# M402X.net
KiCad netlist of a schematic drawn in EAGLE
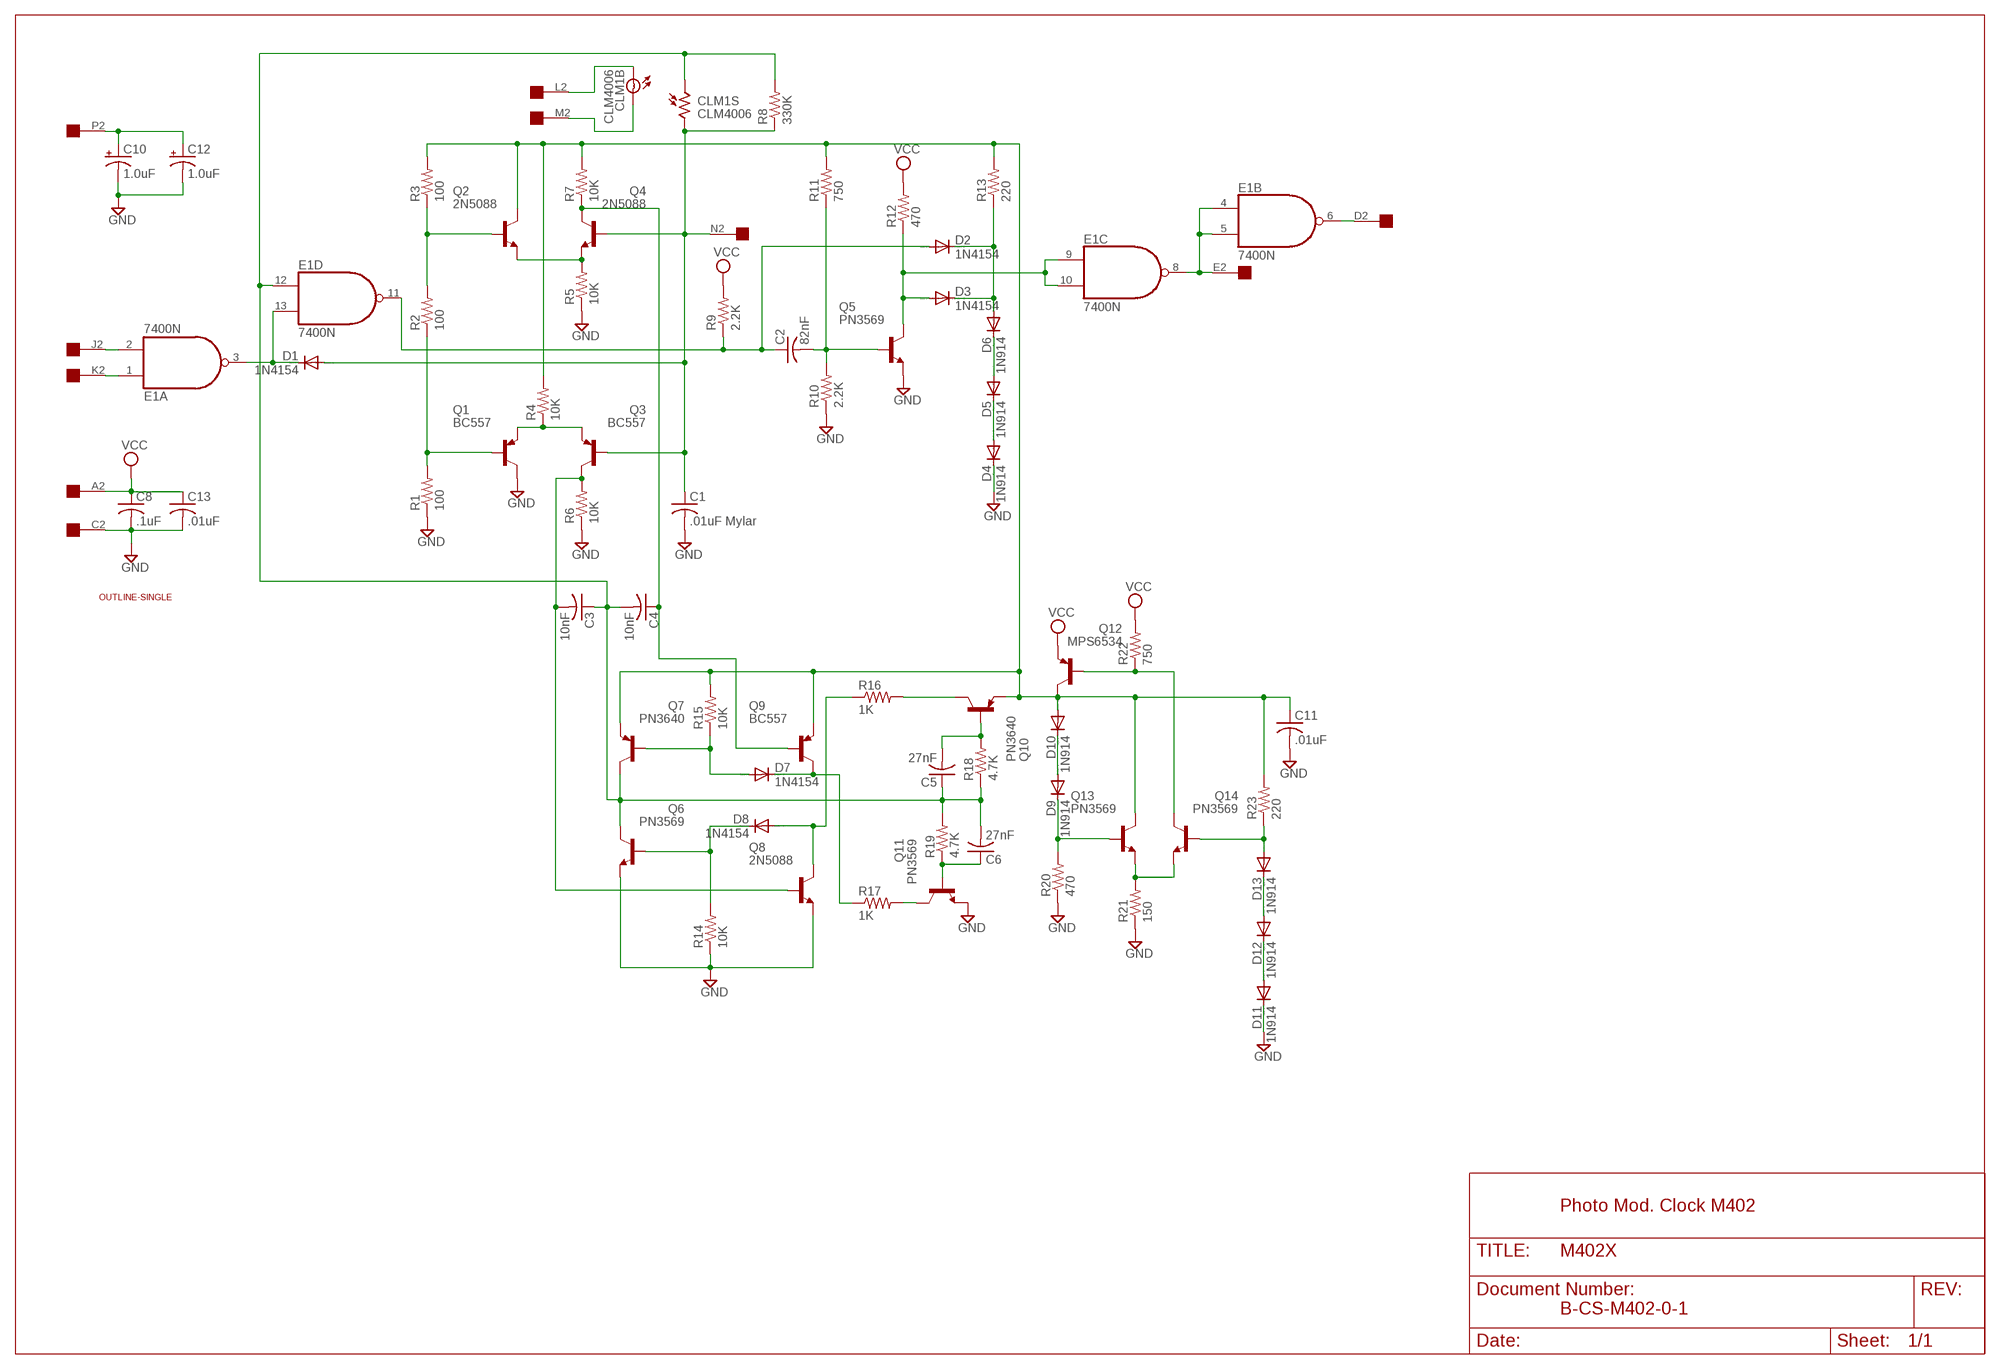
[diagram p0: schematic, sheet 1]

(export (version "E")
  (design (tool "Eeschema 10.0.6"))
  (components
    (comp (ref "C1")
      (value ".01uF Mylar")
      (footprint "eagle-import:C225-062X268")
      (libsource (lib "eagle-import") (part "C-US225-062X268"))
    )
    (comp (ref "C2")
      (value "82nF")
      (footprint "eagle-import:C050-025X075")
      (libsource (lib "eagle-import") (part "C-US050-025X075"))
    )
    (comp (ref "C3")
      (value "10nF")
      (footprint "eagle-import:C075-032X103")
      (libsource (lib "eagle-import") (part "C-US075-032X103"))
    )
    (comp (ref "C4")
      (value "10nF")
      (footprint "eagle-import:C075-032X103")
      (libsource (lib "eagle-import") (part "C-US075-032X103"))
    )
    (comp (ref "C5")
      (value "27nF")
      (footprint "eagle-import:C075-032X103")
      (libsource (lib "eagle-import") (part "C-US075-032X103"))
    )
    (comp (ref "C6")
      (value "27nF")
      (footprint "eagle-import:C075-032X103")
      (libsource (lib "eagle-import") (part "C-US075-032X103"))
    )
    (comp (ref "C8")
      (value ".1uF")
      (footprint "eagle-import:C075-032X103")
      (libsource (lib "eagle-import") (part "C-US075-032X103"))
    )
    (comp (ref "C10")
      (value "1.0uF")
      (footprint "eagle-import:E15-5")
      (libsource (lib "eagle-import") (part "CPOL-USE15-5AXIAL"))
    )
    (comp (ref "C11")
      (value ".01uF")
      (footprint "eagle-import:C050-025X075")
      (libsource (lib "eagle-import") (part "C-US050-025X075"))
    )
    (comp (ref "C12")
      (value "1.0uF")
      (footprint "eagle-import:E15-5")
      (libsource (lib "eagle-import") (part "CPOL-USE15-5AXIAL"))
    )
    (comp (ref "C13")
      (value ".01uF")
      (footprint "eagle-import:C102-043X133")
      (libsource (lib "eagle-import") (part "C-US102-043X133"))
    )
    (comp (ref "CLM1")
      (value "CLM4006")
      (footprint "eagle-import:CLM4006")
      (libsource (lib "eagle-import") (part "CLM4006"))
    )
    (comp (ref "D1")
      (value "1N4154")
      (footprint "eagle-import:DO35-10")
      (libsource (lib "eagle-import") (part "DIODE-DO35-10"))
    )
    (comp (ref "D2")
      (value "1N4154")
      (footprint "eagle-import:DO35-10")
      (libsource (lib "eagle-import") (part "DIODE-DO35-10"))
    )
    (comp (ref "D3")
      (value "1N4154")
      (footprint "eagle-import:DO35-10")
      (libsource (lib "eagle-import") (part "DIODE-DO35-10"))
    )
    (comp (ref "D4")
      (value "1N914")
      (footprint "eagle-import:DO35-10")
      (libsource (lib "eagle-import") (part "DIODE-DO35-10"))
    )
    (comp (ref "D5")
      (value "1N914")
      (footprint "eagle-import:DO35-10")
      (libsource (lib "eagle-import") (part "DIODE-DO35-10"))
    )
    (comp (ref "D6")
      (value "1N914")
      (footprint "eagle-import:DO35-10")
      (libsource (lib "eagle-import") (part "DIODE-DO35-10"))
    )
    (comp (ref "D7")
      (value "1N4154")
      (footprint "eagle-import:DO35-10")
      (libsource (lib "eagle-import") (part "DIODE-DO35-10"))
    )
    (comp (ref "D8")
      (value "1N4154")
      (footprint "eagle-import:DO35-10")
      (libsource (lib "eagle-import") (part "DIODE-DO35-10"))
    )
    (comp (ref "D9")
      (value "1N914")
      (footprint "eagle-import:DO35-10")
      (libsource (lib "eagle-import") (part "DIODE-DO35-10"))
    )
    (comp (ref "D10")
      (value "1N914")
      (footprint "eagle-import:DO35-10")
      (libsource (lib "eagle-import") (part "DIODE-DO35-10"))
    )
    (comp (ref "D11")
      (value "1N914")
      (footprint "eagle-import:DO35-10")
      (libsource (lib "eagle-import") (part "DIODE-DO35-10"))
    )
    (comp (ref "D12")
      (value "1N914")
      (footprint "eagle-import:DO35-10")
      (libsource (lib "eagle-import") (part "DIODE-DO35-10"))
    )
    (comp (ref "D13")
      (value "1N914")
      (footprint "eagle-import:DO35-10")
      (libsource (lib "eagle-import") (part "DIODE-DO35-10"))
    )
    (comp (ref "E1")
      (value "7400N")
      (footprint "eagle-import:DIL14")
      (libsource (lib "eagle-import") (part "7400N"))
    )
    (comp (ref "Q1")
      (value "BC557")
      (footprint "eagle-import:TO5")
      (libsource (lib "eagle-import") (part "-PNP-TO5"))
    )
    (comp (ref "Q2")
      (value "2N5088")
      (footprint "eagle-import:TO5")
      (libsource (lib "eagle-import") (part "-NPN-TO5"))
    )
    (comp (ref "Q3")
      (value "BC557")
      (footprint "eagle-import:TO5")
      (libsource (lib "eagle-import") (part "-PNP-TO5"))
    )
    (comp (ref "Q4")
      (value "2N5088")
      (footprint "eagle-import:TO5")
      (libsource (lib "eagle-import") (part "-NPN-TO5"))
    )
    (comp (ref "Q5")
      (value "PN3569")
      (footprint "eagle-import:TO5")
      (libsource (lib "eagle-import") (part "-NPN-TO5"))
    )
    (comp (ref "Q6")
      (value "PN3569")
      (footprint "eagle-import:TO5")
      (libsource (lib "eagle-import") (part "-NPN-TO5"))
    )
    (comp (ref "Q7")
      (value "PN3640")
      (footprint "eagle-import:TO5")
      (libsource (lib "eagle-import") (part "-PNP-TO5"))
    )
    (comp (ref "Q8")
      (value "2N5088")
      (footprint "eagle-import:TO5")
      (libsource (lib "eagle-import") (part "-NPN-TO5"))
    )
    (comp (ref "Q9")
      (value "BC557")
      (footprint "eagle-import:TO5")
      (libsource (lib "eagle-import") (part "-PNP-TO5"))
    )
    (comp (ref "Q10")
      (value "PN3640")
      (footprint "eagle-import:TO5")
      (libsource (lib "eagle-import") (part "-PNP-TO5"))
    )
    (comp (ref "Q11")
      (value "PN3569")
      (footprint "eagle-import:TO5")
      (libsource (lib "eagle-import") (part "-NPN-TO5"))
    )
    (comp (ref "Q12")
      (value "MPS6534")
      (footprint "eagle-import:TO5")
      (libsource (lib "eagle-import") (part "-PNP-TO5"))
    )
    (comp (ref "Q13")
      (value "PN3569")
      (footprint "eagle-import:TO5")
      (libsource (lib "eagle-import") (part "-NPN-TO5"))
    )
    (comp (ref "Q14")
      (value "PN3569")
      (footprint "eagle-import:TO5")
      (libsource (lib "eagle-import") (part "-NPN-TO5"))
    )
    (comp (ref "R1")
      (value "100")
      (footprint "eagle-import:0207_10")
      (libsource (lib "eagle-import") (part "R-US_0207/10"))
    )
    (comp (ref "R2")
      (value "100")
      (footprint "eagle-import:0207_10")
      (libsource (lib "eagle-import") (part "R-US_0207/10"))
    )
    (comp (ref "R3")
      (value "100")
      (footprint "eagle-import:0207_10")
      (libsource (lib "eagle-import") (part "R-US_0207/10"))
    )
    (comp (ref "R4")
      (value "10K")
      (footprint "eagle-import:0207_10")
      (libsource (lib "eagle-import") (part "R-US_0207/10"))
    )
    (comp (ref "R5")
      (value "10K")
      (footprint "eagle-import:0207_10")
      (libsource (lib "eagle-import") (part "R-US_0207/10"))
    )
    (comp (ref "R6")
      (value "10K")
      (footprint "eagle-import:0207_10")
      (libsource (lib "eagle-import") (part "R-US_0207/10"))
    )
    (comp (ref "R7")
      (value "10K")
      (footprint "eagle-import:0207_10")
      (libsource (lib "eagle-import") (part "R-US_0207/10"))
    )
    (comp (ref "R8")
      (value "330K")
      (footprint "eagle-import:0207_10")
      (libsource (lib "eagle-import") (part "R-US_0207/10"))
    )
    (comp (ref "R9")
      (value "2.2K")
      (footprint "eagle-import:0207_10")
      (libsource (lib "eagle-import") (part "R-US_0207/10"))
    )
    (comp (ref "R10")
      (value "2.2K")
      (footprint "eagle-import:0207_10")
      (libsource (lib "eagle-import") (part "R-US_0207/10"))
    )
    (comp (ref "R11")
      (value "750")
      (footprint "eagle-import:0207_10")
      (libsource (lib "eagle-import") (part "R-US_0207/10"))
    )
    (comp (ref "R12")
      (value "470")
      (footprint "eagle-import:0207_10")
      (libsource (lib "eagle-import") (part "R-US_0207/10"))
    )
    (comp (ref "R13")
      (value "220")
      (footprint "eagle-import:0207_10")
      (libsource (lib "eagle-import") (part "R-US_0207/10"))
    )
    (comp (ref "R14")
      (value "10K")
      (footprint "eagle-import:0207_10")
      (libsource (lib "eagle-import") (part "R-US_0207/10"))
    )
    (comp (ref "R15")
      (value "10K")
      (footprint "eagle-import:0207_10")
      (libsource (lib "eagle-import") (part "R-US_0207/10"))
    )
    (comp (ref "R16")
      (value "1K")
      (footprint "eagle-import:0207_10")
      (libsource (lib "eagle-import") (part "R-US_0207/10"))
    )
    (comp (ref "R17")
      (value "1K")
      (footprint "eagle-import:0207_10")
      (libsource (lib "eagle-import") (part "R-US_0207/10"))
    )
    (comp (ref "R18")
      (value "4.7K")
      (footprint "eagle-import:0207_10")
      (libsource (lib "eagle-import") (part "R-US_0207/10"))
    )
    (comp (ref "R19")
      (value "4.7K")
      (footprint "eagle-import:0207_10")
      (libsource (lib "eagle-import") (part "R-US_0207/10"))
    )
    (comp (ref "R20")
      (value "470")
      (footprint "eagle-import:0207_10")
      (libsource (lib "eagle-import") (part "R-US_0207/10"))
    )
    (comp (ref "R21")
      (value "150")
      (footprint "eagle-import:0207_10")
      (libsource (lib "eagle-import") (part "R-US_0207/10"))
    )
    (comp (ref "R22")
      (value "750")
      (footprint "eagle-import:0207_10")
      (libsource (lib "eagle-import") (part "R-US_0207/10"))
    )
    (comp (ref "R23")
      (value "220")
      (footprint "eagle-import:0207_10")
      (libsource (lib "eagle-import") (part "R-US_0207/10"))
    )
    (comp (ref "U$1")
      (value "OUTLINE-SINGLE")
      (footprint "eagle-import:SINGLE")
      (libsource (lib "eagle-import") (part "OUTLINE-SINGLE"))
    )
    (comp (ref "U$3")
      (value "EDGE-1")
      (footprint "eagle-import:EDGE-CON1")
      (libsource (lib "eagle-import") (part "EDGE-1"))
    )
  )
  (nets
    (net (code "1") (name "GND") (class "Default")
      (node (ref "C1") (pin "2") (pinfunction "2_2") (pintype "passive"))
      (node (ref "C10") (pin "-") (pinfunction "-_-") (pintype "passive"))
      (node (ref "C11") (pin "2") (pinfunction "2_2") (pintype "passive"))
      (node (ref "C12") (pin "-") (pinfunction "-_-") (pintype "passive"))
      (node (ref "C13") (pin "2") (pinfunction "2_2") (pintype "passive"))
      (node (ref "C8") (pin "2") (pinfunction "2_2") (pintype "passive"))
      (node (ref "D11") (pin "C") (pinfunction "C_C") (pintype "passive"))
      (node (ref "D4") (pin "C") (pinfunction "C_C") (pintype "passive"))
      (node (ref "Q1") (pin "3") (pinfunction "C_3") (pintype "passive"))
      (node (ref "Q11") (pin "1") (pinfunction "E_1") (pintype "passive"))
      (node (ref "Q5") (pin "1") (pinfunction "E_1") (pintype "passive"))
      (node (ref "Q6") (pin "1") (pinfunction "E_1") (pintype "passive"))
      (node (ref "Q8") (pin "1") (pinfunction "E_1") (pintype "passive"))
      (node (ref "R1") (pin "1") (pinfunction "1_1") (pintype "passive"))
      (node (ref "R10") (pin "1") (pinfunction "1_1") (pintype "passive"))
      (node (ref "R14") (pin "1") (pinfunction "1_1") (pintype "passive"))
      (node (ref "R20") (pin "1") (pinfunction "1_1") (pintype "passive"))
      (node (ref "R21") (pin "1") (pinfunction "1_1") (pintype "passive"))
      (node (ref "R5") (pin "1") (pinfunction "1_1") (pintype "passive"))
      (node (ref "R6") (pin "1") (pinfunction "1_1") (pintype "passive"))
      (node (ref "U$3") (pin "C2") (pinfunction "1_C2") (pintype "bidirectional"))
    )
    (net (code "2") (name "Net-(CLM1A-A)") (class "Default")
      (node (ref "CLM1") (pin "B1") (pinfunction "A_B1") (pintype "passive"))
      (node (ref "U$3") (pin "M2") (pinfunction "1_M2") (pintype "bidirectional"))
    )
    (net (code "3") (name "Net-(CLM1A-B)") (class "Default")
      (node (ref "CLM1") (pin "B2") (pinfunction "B_B2") (pintype "passive"))
      (node (ref "U$3") (pin "L2") (pinfunction "1_L2") (pintype "bidirectional"))
    )
    (net (code "4") (name "Net-(CLM1B-1)") (class "Default")
      (node (ref "C3") (pin "1") (pinfunction "1_1") (pintype "passive"))
      (node (ref "C4") (pin "2") (pinfunction "2_2") (pintype "passive"))
      (node (ref "C5") (pin "1") (pinfunction "1_1") (pintype "passive"))
      (node (ref "C6") (pin "2") (pinfunction "2_2") (pintype "passive"))
      (node (ref "CLM1") (pin "S1") (pinfunction "1_S1") (pintype "passive"))
      (node (ref "E1") (pin "12") (pinfunction "I0_12") (pintype "input"))
      (node (ref "Q6") (pin "3") (pinfunction "C_3") (pintype "passive"))
      (node (ref "Q7") (pin "3") (pinfunction "C_3") (pintype "passive"))
      (node (ref "R18") (pin "1") (pinfunction "1_1") (pintype "passive"))
      (node (ref "R19") (pin "2") (pinfunction "2_2") (pintype "passive"))
      (node (ref "R8") (pin "2") (pinfunction "2_2") (pintype "passive"))
    )
    (net (code "5") (name "Net-(CLM1B-2)") (class "Default")
      (node (ref "C1") (pin "1") (pinfunction "1_1") (pintype "passive"))
      (node (ref "CLM1") (pin "S2") (pinfunction "2_S2") (pintype "passive"))
      (node (ref "D1") (pin "A") (pinfunction "A_A") (pintype "passive"))
      (node (ref "Q3") (pin "2") (pinfunction "B_2") (pintype "passive"))
      (node (ref "Q4") (pin "2") (pinfunction "B_2") (pintype "passive"))
      (node (ref "R8") (pin "1") (pinfunction "1_1") (pintype "passive"))
      (node (ref "U$3") (pin "N2") (pinfunction "1_N2") (pintype "bidirectional"))
    )
    (net (code "6") (name "Net-(D2-PadC)") (class "Default")
      (node (ref "D2") (pin "C") (pinfunction "C_C") (pintype "passive"))
      (node (ref "D3") (pin "C") (pinfunction "C_C") (pintype "passive"))
      (node (ref "D6") (pin "A") (pinfunction "A_A") (pintype "passive"))
      (node (ref "R13") (pin "1") (pinfunction "1_1") (pintype "passive"))
    )
    (net (code "7") (name "Net-(D4-PadA)") (class "Default")
      (node (ref "D4") (pin "A") (pinfunction "A_A") (pintype "passive"))
      (node (ref "D5") (pin "C") (pinfunction "C_C") (pintype "passive"))
    )
    (net (code "8") (name "Net-(D5-PadA)") (class "Default")
      (node (ref "D5") (pin "A") (pinfunction "A_A") (pintype "passive"))
      (node (ref "D6") (pin "C") (pinfunction "C_C") (pintype "passive"))
    )
    (net (code "9") (name "Net-(D10-PadC)") (class "Default")
      (node (ref "D10") (pin "C") (pinfunction "C_C") (pintype "passive"))
      (node (ref "D9") (pin "A") (pinfunction "A_A") (pintype "passive"))
    )
    (net (code "10") (name "Net-(D11-PadA)") (class "Default")
      (node (ref "D11") (pin "A") (pinfunction "A_A") (pintype "passive"))
      (node (ref "D12") (pin "C") (pinfunction "C_C") (pintype "passive"))
    )
    (net (code "11") (name "Net-(D12-PadA)") (class "Default")
      (node (ref "D12") (pin "A") (pinfunction "A_A") (pintype "passive"))
      (node (ref "D13") (pin "C") (pinfunction "C_C") (pintype "passive"))
    )
    (net (code "12") (name "Net-(E1A-I0)") (class "Default")
      (node (ref "E1") (pin "1") (pinfunction "I0_1") (pintype "input"))
      (node (ref "U$3") (pin "K2") (pinfunction "1_K2") (pintype "bidirectional"))
    )
    (net (code "13") (name "Net-(E1A-I1)") (class "Default")
      (node (ref "E1") (pin "2") (pinfunction "I1_2") (pintype "input"))
      (node (ref "U$3") (pin "J2") (pinfunction "1_J2") (pintype "bidirectional"))
    )
    (net (code "14") (name "Net-(E1A-O)") (class "Default")
      (node (ref "D1") (pin "C") (pinfunction "C_C") (pintype "passive"))
      (node (ref "E1") (pin "13") (pinfunction "I1_13") (pintype "input"))
      (node (ref "E1") (pin "3") (pinfunction "O_3") (pintype "output"))
    )
    (net (code "15") (name "Net-(E1B-I0)") (class "Default")
      (node (ref "E1") (pin "4") (pinfunction "I0_4") (pintype "input"))
      (node (ref "E1") (pin "5") (pinfunction "I1_5") (pintype "input"))
      (node (ref "E1") (pin "8") (pinfunction "O_8") (pintype "output"))
      (node (ref "U$3") (pin "E2") (pinfunction "1_E2") (pintype "bidirectional"))
    )
    (net (code "16") (name "Net-(E1B-O)") (class "Default")
      (node (ref "E1") (pin "6") (pinfunction "O_6") (pintype "output"))
      (node (ref "U$3") (pin "D2") (pinfunction "1_D2") (pintype "bidirectional"))
    )
    (net (code "17") (name "Net-(E1C-I0)") (class "Default")
      (node (ref "D3") (pin "A") (pinfunction "A_A") (pintype "passive"))
      (node (ref "E1") (pin "10") (pinfunction "I1_10") (pintype "input"))
      (node (ref "E1") (pin "9") (pinfunction "I0_9") (pintype "input"))
      (node (ref "Q5") (pin "3") (pinfunction "C_3") (pintype "passive"))
      (node (ref "R12") (pin "1") (pinfunction "1_1") (pintype "passive"))
    )
    (net (code "18") (name "Net-(E1D-O)") (class "Default")
      (node (ref "C2") (pin "1") (pinfunction "1_1") (pintype "passive"))
      (node (ref "D2") (pin "A") (pinfunction "A_A") (pintype "passive"))
      (node (ref "E1") (pin "11") (pinfunction "O_11") (pintype "output"))
      (node (ref "R9") (pin "1") (pinfunction "1_1") (pintype "passive"))
    )
    (net (code "19") (name "Net-(Q1-B)") (class "Default")
      (node (ref "Q1") (pin "2") (pinfunction "B_2") (pintype "passive"))
      (node (ref "R1") (pin "2") (pinfunction "2_2") (pintype "passive"))
      (node (ref "R2") (pin "1") (pinfunction "1_1") (pintype "passive"))
    )
    (net (code "20") (name "Net-(Q1-E)") (class "Default")
      (node (ref "Q1") (pin "1") (pinfunction "E_1") (pintype "passive"))
      (node (ref "Q3") (pin "1") (pinfunction "E_1") (pintype "passive"))
      (node (ref "R4") (pin "1") (pinfunction "1_1") (pintype "passive"))
    )
    (net (code "21") (name "Net-(Q2-B)") (class "Default")
      (node (ref "Q2") (pin "2") (pinfunction "B_2") (pintype "passive"))
      (node (ref "R2") (pin "2") (pinfunction "2_2") (pintype "passive"))
      (node (ref "R3") (pin "1") (pinfunction "1_1") (pintype "passive"))
    )
    (net (code "22") (name "Net-(Q2-E)") (class "Default")
      (node (ref "Q2") (pin "1") (pinfunction "E_1") (pintype "passive"))
      (node (ref "Q4") (pin "1") (pinfunction "E_1") (pintype "passive"))
      (node (ref "R5") (pin "2") (pinfunction "2_2") (pintype "passive"))
    )
    (net (code "23") (name "Net-(Q3-C)") (class "Default")
      (node (ref "C3") (pin "2") (pinfunction "2_2") (pintype "passive"))
      (node (ref "Q3") (pin "3") (pinfunction "C_3") (pintype "passive"))
      (node (ref "Q8") (pin "2") (pinfunction "B_2") (pintype "passive"))
      (node (ref "R6") (pin "2") (pinfunction "2_2") (pintype "passive"))
    )
    (net (code "24") (name "Net-(Q4-C)") (class "Default")
      (node (ref "C4") (pin "1") (pinfunction "1_1") (pintype "passive"))
      (node (ref "Q4") (pin "3") (pinfunction "C_3") (pintype "passive"))
      (node (ref "Q9") (pin "2") (pinfunction "B_2") (pintype "passive"))
      (node (ref "R7") (pin "1") (pinfunction "1_1") (pintype "passive"))
    )
    (net (code "25") (name "Net-(Q5-B)") (class "Default")
      (node (ref "C2") (pin "2") (pinfunction "2_2") (pintype "passive"))
      (node (ref "Q5") (pin "2") (pinfunction "B_2") (pintype "passive"))
      (node (ref "R10") (pin "2") (pinfunction "2_2") (pintype "passive"))
      (node (ref "R11") (pin "1") (pinfunction "1_1") (pintype "passive"))
    )
    (net (code "26") (name "Net-(Q6-B)") (class "Default")
      (node (ref "D8") (pin "C") (pinfunction "C_C") (pintype "passive"))
      (node (ref "Q6") (pin "2") (pinfunction "B_2") (pintype "passive"))
      (node (ref "R14") (pin "2") (pinfunction "2_2") (pintype "passive"))
    )
    (net (code "27") (name "Net-(Q7-B)") (class "Default")
      (node (ref "D7") (pin "A") (pinfunction "A_A") (pintype "passive"))
      (node (ref "Q7") (pin "2") (pinfunction "B_2") (pintype "passive"))
      (node (ref "R15") (pin "1") (pinfunction "1_1") (pintype "passive"))
    )
    (net (code "28") (name "Net-(Q8-C)") (class "Default")
      (node (ref "D8") (pin "A") (pinfunction "A_A") (pintype "passive"))
      (node (ref "Q8") (pin "3") (pinfunction "C_3") (pintype "passive"))
      (node (ref "R16") (pin "1") (pinfunction "1_1") (pintype "passive"))
    )
    (net (code "29") (name "Net-(Q9-C)") (class "Default")
      (node (ref "D7") (pin "C") (pinfunction "C_C") (pintype "passive"))
      (node (ref "Q9") (pin "3") (pinfunction "C_3") (pintype "passive"))
      (node (ref "R17") (pin "1") (pinfunction "1_1") (pintype "passive"))
    )
    (net (code "30") (name "Net-(Q10-B)") (class "Default")
      (node (ref "C5") (pin "2") (pinfunction "2_2") (pintype "passive"))
      (node (ref "Q10") (pin "2") (pinfunction "B_2") (pintype "passive"))
      (node (ref "R18") (pin "2") (pinfunction "2_2") (pintype "passive"))
    )
    (net (code "31") (name "Net-(Q10-C)") (class "Default")
      (node (ref "Q10") (pin "3") (pinfunction "C_3") (pintype "passive"))
      (node (ref "R16") (pin "2") (pinfunction "2_2") (pintype "passive"))
    )
    (net (code "32") (name "Net-(Q10-E)") (class "Default")
      (node (ref "C11") (pin "1") (pinfunction "1_1") (pintype "passive"))
      (node (ref "D10") (pin "A") (pinfunction "A_A") (pintype "passive"))
      (node (ref "Q10") (pin "1") (pinfunction "E_1") (pintype "passive"))
      (node (ref "Q12") (pin "3") (pinfunction "C_3") (pintype "passive"))
      (node (ref "Q13") (pin "3") (pinfunction "C_3") (pintype "passive"))
      (node (ref "Q2") (pin "3") (pinfunction "C_3") (pintype "passive"))
      (node (ref "Q7") (pin "1") (pinfunction "E_1") (pintype "passive"))
      (node (ref "Q9") (pin "1") (pinfunction "E_1") (pintype "passive"))
      (node (ref "R11") (pin "2") (pinfunction "2_2") (pintype "passive"))
      (node (ref "R13") (pin "2") (pinfunction "2_2") (pintype "passive"))
      (node (ref "R15") (pin "2") (pinfunction "2_2") (pintype "passive"))
      (node (ref "R23") (pin "2") (pinfunction "2_2") (pintype "passive"))
      (node (ref "R3") (pin "2") (pinfunction "2_2") (pintype "passive"))
      (node (ref "R4") (pin "2") (pinfunction "2_2") (pintype "passive"))
      (node (ref "R7") (pin "2") (pinfunction "2_2") (pintype "passive"))
    )
    (net (code "33") (name "Net-(Q11-B)") (class "Default")
      (node (ref "C6") (pin "1") (pinfunction "1_1") (pintype "passive"))
      (node (ref "Q11") (pin "2") (pinfunction "B_2") (pintype "passive"))
      (node (ref "R19") (pin "1") (pinfunction "1_1") (pintype "passive"))
    )
    (net (code "34") (name "Net-(Q11-C)") (class "Default")
      (node (ref "Q11") (pin "3") (pinfunction "C_3") (pintype "passive"))
      (node (ref "R17") (pin "2") (pinfunction "2_2") (pintype "passive"))
    )
    (net (code "35") (name "Net-(Q12-B)") (class "Default")
      (node (ref "Q12") (pin "2") (pinfunction "B_2") (pintype "passive"))
      (node (ref "Q14") (pin "3") (pinfunction "C_3") (pintype "passive"))
      (node (ref "R22") (pin "1") (pinfunction "1_1") (pintype "passive"))
    )
    (net (code "36") (name "Net-(Q13-B)") (class "Default")
      (node (ref "D9") (pin "C") (pinfunction "C_C") (pintype "passive"))
      (node (ref "Q13") (pin "2") (pinfunction "B_2") (pintype "passive"))
      (node (ref "R20") (pin "2") (pinfunction "2_2") (pintype "passive"))
    )
    (net (code "37") (name "Net-(Q13-E)") (class "Default")
      (node (ref "Q13") (pin "1") (pinfunction "E_1") (pintype "passive"))
      (node (ref "Q14") (pin "1") (pinfunction "E_1") (pintype "passive"))
      (node (ref "R21") (pin "2") (pinfunction "2_2") (pintype "passive"))
    )
    (net (code "38") (name "Net-(Q14-B)") (class "Default")
      (node (ref "D13") (pin "A") (pinfunction "A_A") (pintype "passive"))
      (node (ref "Q14") (pin "2") (pinfunction "B_2") (pintype "passive"))
      (node (ref "R23") (pin "1") (pinfunction "1_1") (pintype "passive"))
    )
    (net (code "39") (name "Net-(U$3M-1)") (class "Default")
      (node (ref "C10") (pin "+") (pinfunction "+_+") (pintype "passive"))
      (node (ref "C12") (pin "+") (pinfunction "+_+") (pintype "passive"))
      (node (ref "U$3") (pin "P2") (pinfunction "1_P2") (pintype "bidirectional"))
    )
    (net (code "40") (name "VCC") (class "Default")
      (node (ref "C13") (pin "1") (pinfunction "1_1") (pintype "passive"))
      (node (ref "C8") (pin "1") (pinfunction "1_1") (pintype "passive"))
      (node (ref "Q12") (pin "1") (pinfunction "E_1") (pintype "passive"))
      (node (ref "R12") (pin "2") (pinfunction "2_2") (pintype "passive"))
      (node (ref "R22") (pin "2") (pinfunction "2_2") (pintype "passive"))
      (node (ref "R9") (pin "2") (pinfunction "2_2") (pintype "passive"))
      (node (ref "U$3") (pin "A2") (pinfunction "1_A2") (pintype "bidirectional"))
    )
  )
)
